# petitAVR-v1.net
KiCad netlist of a schematic drawn in EAGLE
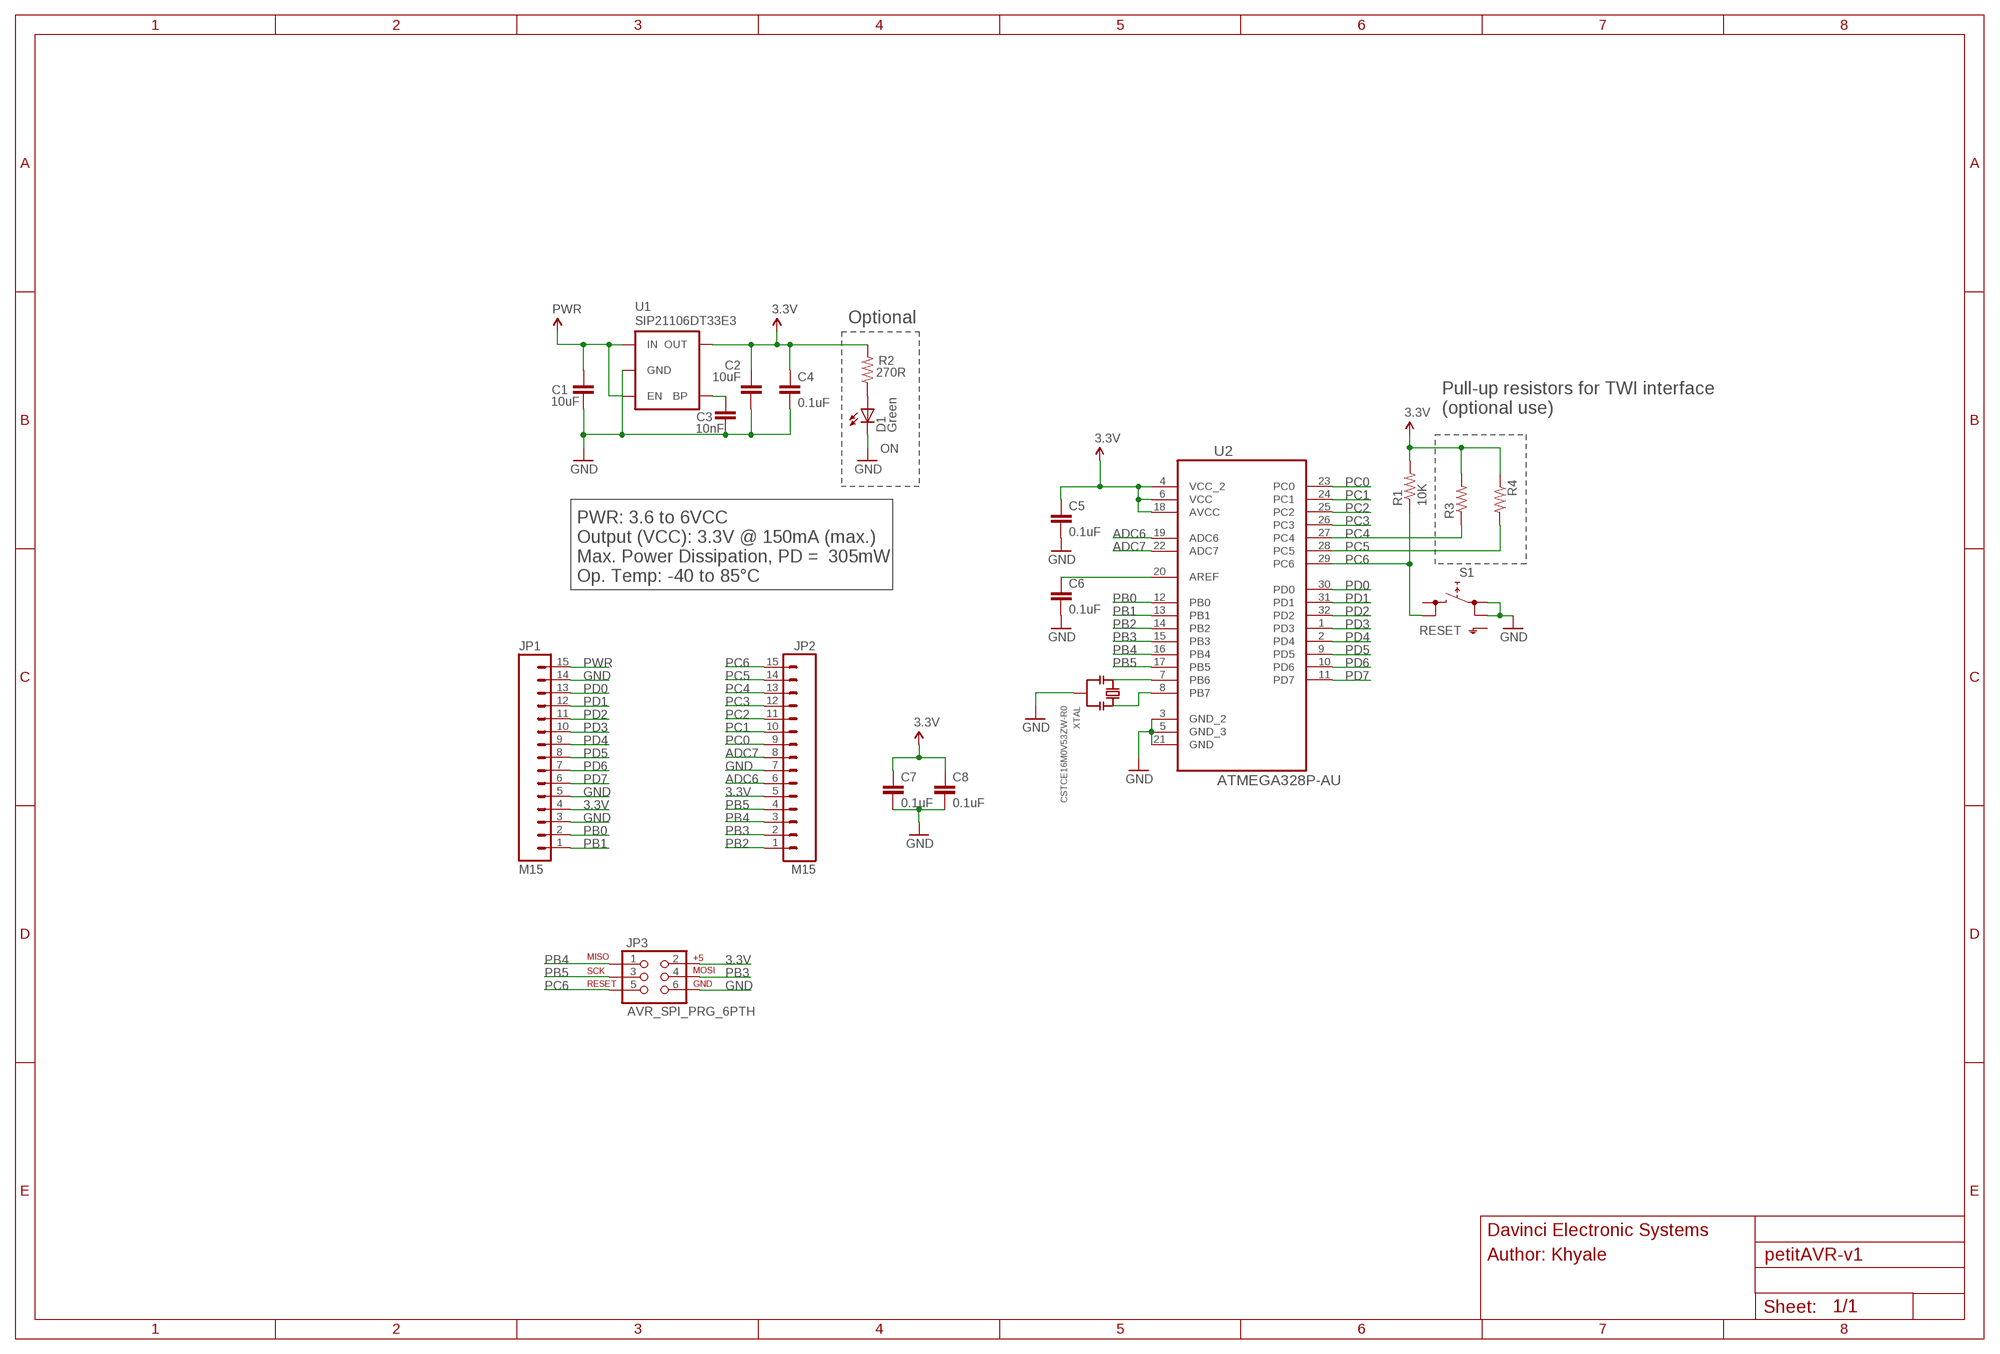
[diagram p0: schematic, sheet 1]

(export (version "E")
  (design (tool "Eeschema 10.0.6"))
  (components
    (comp (ref "C1")
      (value "10uF")
      (footprint "eagle-import:0805")
      (fields (field (name "MPN") "LMK212AB7106MG-T"))
      (libsource (lib "eagle-import") (part "CAP0805"))
    )
    (comp (ref "C2")
      (value "10uF")
      (footprint "eagle-import:0805")
      (fields (field (name "MPN") "LMK212AB7106MG-T"))
      (libsource (lib "eagle-import") (part "CAP0805"))
    )
    (comp (ref "C3")
      (value "10nF")
      (footprint "eagle-import:0805")
      (fields (field (name "MPN") "VJ0805Y103JXQCW1BC"))
      (libsource (lib "eagle-import") (part "CAP0805"))
    )
    (comp (ref "C4")
      (value "0.1uF")
      (footprint "eagle-import:0603-CAP")
      (fields (field (name "MPN") "VJ0603Y104KXJCW1BC"))
      (libsource (lib "eagle-import") (part "SparkFun-Passives_CAP0603-CAP"))
    )
    (comp (ref "C5")
      (value "0.1uF")
      (footprint "eagle-import:0603-CAP")
      (fields (field (name "MPN") "VJ0603Y104KXJCW1BC"))
      (libsource (lib "eagle-import") (part "SparkFun-Passives_CAP0603-CAP"))
    )
    (comp (ref "C6")
      (value "0.1uF")
      (footprint "eagle-import:0603-CAP")
      (fields (field (name "MPN") "VJ0603Y104KXJCW1BC"))
      (libsource (lib "eagle-import") (part "SparkFun-Passives_CAP0603-CAP"))
    )
    (comp (ref "C7")
      (value "0.1uF")
      (footprint "eagle-import:0603-CAP")
      (fields (field (name "MPN") "VJ0603Y104KXJCW1BC"))
      (libsource (lib "eagle-import") (part "SparkFun-Passives_CAP0603-CAP"))
    )
    (comp (ref "C8")
      (value "0.1uF")
      (footprint "eagle-import:0603-CAP")
      (fields (field (name "MPN") "VJ0603Y104KXJCW1BC"))
      (libsource (lib "eagle-import") (part "SparkFun-Passives_CAP0603-CAP"))
    )
    (comp (ref "D1")
      (value "Green")
      (footprint "eagle-import:LED-0603")
      (fields (field (name "MPN") "VLMG1300-GS08"))
      (libsource (lib "eagle-import") (part "LED0603"))
    )
    (comp (ref "JP1")
      (value "M15")
      (footprint "eagle-import:1X15")
      (fields (field (name "MPN") "22-28-4151"))
      (libsource (lib "eagle-import") (part "M15"))
    )
    (comp (ref "JP2")
      (value "M15")
      (footprint "eagle-import:1X15")
      (fields (field (name "MPN") "22-28-4151"))
      (libsource (lib "eagle-import") (part "M15"))
    )
    (comp (ref "JP3")
      (value "AVR_SPI_PRG_6PTH")
      (footprint "eagle-import:2X3")
      (fields (field (name "MPN") "103328-3"))
      (libsource (lib "eagle-import") (part "AVR_SPI_PRG_6PTH"))
    )
    (comp (ref "R1")
      (value "10K")
      (footprint "eagle-import:0603-RES")
      (fields (field (name "MPN") "ERJ-3EKF1002V"))
      (libsource (lib "eagle-import") (part "RESISTOR0603"))
    )
    (comp (ref "R2")
      (value "270R")
      (footprint "eagle-import:0805")
      (fields (field (name "MPN") "ERJ-6GEYJ271V"))
      (libsource (lib "eagle-import") (part "RESISTOR0805-RES"))
    )
    (comp (ref "R3")
      (value "RESISTOR0603-RES")
      (footprint "eagle-import:0603-RES")
      (libsource (lib "eagle-import") (part "RESISTOR0603-RES"))
    )
    (comp (ref "R4")
      (value "RESISTOR0603")
      (footprint "eagle-import:0603-RES")
      (libsource (lib "eagle-import") (part "RESISTOR0603"))
    )
    (comp (ref "S1")
      (value "RESET")
      (footprint "eagle-import:SKHMPXE010")
      (fields (field (name "MPN") "FSM1LPATR"))
      (libsource (lib "eagle-import") (part "SKHMPE010S"))
    )
    (comp (ref "U1")
      (value "SIP21106DT33E3")
      (footprint "eagle-import:SOT23-5")
      (fields (field (name "MPN") "SIP21106DT-33-E3"))
      (libsource (lib "eagle-import") (part "V_REG_LDOSMD"))
    )
    (comp (ref "U2")
      (value "ATMEGA328P-AU")
      (footprint "eagle-import:QFP80P900X900X120-32N")
      (libsource (lib "eagle-import") (part "ATMEGA328P-AU"))
    )
    (comp (ref "XTAL")
      (value "CSTCE16M0V53ZW-R0")
      (footprint "eagle-import:CSTCE_V")
      (libsource (lib "eagle-import") (part "CSTCE16M0V53ZW-R0"))
    )
  )
  (nets
    (net (code "1") (name "/ADC6") (class "Default")
      (node (ref "JP2") (pin "6") (pinfunction "6_6") (pintype "passive"))
      (node (ref "U2") (pin "19") (pinfunction "ADC6_19") (pintype "input"))
    )
    (net (code "2") (name "/ADC7") (class "Default")
      (node (ref "JP2") (pin "8") (pinfunction "8_8") (pintype "passive"))
      (node (ref "U2") (pin "22") (pinfunction "ADC7_22") (pintype "input"))
    )
    (net (code "3") (name "/PB0") (class "Default")
      (node (ref "JP1") (pin "2") (pinfunction "2_2") (pintype "passive"))
      (node (ref "U2") (pin "12") (pinfunction "PB0_12") (pintype "bidirectional"))
    )
    (net (code "4") (name "/PB1") (class "Default")
      (node (ref "JP1") (pin "1") (pinfunction "1_1") (pintype "passive"))
      (node (ref "U2") (pin "13") (pinfunction "PB1_13") (pintype "bidirectional"))
    )
    (net (code "5") (name "/PB2") (class "Default")
      (node (ref "JP2") (pin "1") (pinfunction "1_1") (pintype "passive"))
      (node (ref "U2") (pin "14") (pinfunction "PB2_14") (pintype "bidirectional"))
    )
    (net (code "6") (name "/PB3") (class "Default")
      (node (ref "JP2") (pin "2") (pinfunction "2_2") (pintype "passive"))
      (node (ref "JP3") (pin "4") (pinfunction "4_4") (pintype "passive"))
      (node (ref "U2") (pin "15") (pinfunction "PB3_15") (pintype "bidirectional"))
    )
    (net (code "7") (name "/PB4") (class "Default")
      (node (ref "JP2") (pin "3") (pinfunction "3_3") (pintype "passive"))
      (node (ref "JP3") (pin "1") (pinfunction "1_1") (pintype "passive"))
      (node (ref "U2") (pin "16") (pinfunction "PB4_16") (pintype "bidirectional"))
    )
    (net (code "8") (name "/PB5") (class "Default")
      (node (ref "JP2") (pin "4") (pinfunction "4_4") (pintype "passive"))
      (node (ref "JP3") (pin "3") (pinfunction "3_3") (pintype "passive"))
      (node (ref "U2") (pin "17") (pinfunction "PB5_17") (pintype "bidirectional"))
    )
    (net (code "9") (name "/PC0") (class "Default")
      (node (ref "JP2") (pin "9") (pinfunction "9_9") (pintype "passive"))
      (node (ref "U2") (pin "23") (pinfunction "PC0_23") (pintype "bidirectional"))
    )
    (net (code "10") (name "/PC1") (class "Default")
      (node (ref "JP2") (pin "10") (pinfunction "10_10") (pintype "passive"))
      (node (ref "U2") (pin "24") (pinfunction "PC1_24") (pintype "bidirectional"))
    )
    (net (code "11") (name "/PC2") (class "Default")
      (node (ref "JP2") (pin "11") (pinfunction "11_11") (pintype "passive"))
      (node (ref "U2") (pin "25") (pinfunction "PC2_25") (pintype "bidirectional"))
    )
    (net (code "12") (name "/PC3") (class "Default")
      (node (ref "JP2") (pin "12") (pinfunction "12_12") (pintype "passive"))
      (node (ref "U2") (pin "26") (pinfunction "PC3_26") (pintype "bidirectional"))
    )
    (net (code "13") (name "/PC4") (class "Default")
      (node (ref "JP2") (pin "13") (pinfunction "13_13") (pintype "passive"))
      (node (ref "R3") (pin "1") (pinfunction "1_1") (pintype "passive"))
      (node (ref "U2") (pin "27") (pinfunction "PC4_27") (pintype "bidirectional"))
    )
    (net (code "14") (name "/PC5") (class "Default")
      (node (ref "JP2") (pin "14") (pinfunction "14_14") (pintype "passive"))
      (node (ref "R4") (pin "2") (pinfunction "2_2") (pintype "passive"))
      (node (ref "U2") (pin "28") (pinfunction "PC5_28") (pintype "bidirectional"))
    )
    (net (code "15") (name "/PC6") (class "Default")
      (node (ref "JP2") (pin "15") (pinfunction "15_15") (pintype "passive"))
      (node (ref "JP3") (pin "5") (pinfunction "5_5") (pintype "passive"))
      (node (ref "R1") (pin "1") (pinfunction "1_1") (pintype "passive"))
      (node (ref "S1") (pin "4") (pinfunction "2.2_4") (pintype "passive"))
      (node (ref "U2") (pin "29") (pinfunction "PC6_29") (pintype "bidirectional"))
    )
    (net (code "16") (name "/PD0") (class "Default")
      (node (ref "JP1") (pin "13") (pinfunction "13_13") (pintype "passive"))
      (node (ref "U2") (pin "30") (pinfunction "PD0_30") (pintype "bidirectional"))
    )
    (net (code "17") (name "/PD1") (class "Default")
      (node (ref "JP1") (pin "12") (pinfunction "12_12") (pintype "passive"))
      (node (ref "U2") (pin "31") (pinfunction "PD1_31") (pintype "bidirectional"))
    )
    (net (code "18") (name "/PD2") (class "Default")
      (node (ref "JP1") (pin "11") (pinfunction "11_11") (pintype "passive"))
      (node (ref "U2") (pin "32") (pinfunction "PD2_32") (pintype "bidirectional"))
    )
    (net (code "19") (name "/PD3") (class "Default")
      (node (ref "JP1") (pin "10") (pinfunction "10_10") (pintype "passive"))
      (node (ref "U2") (pin "1") (pinfunction "PD3_1") (pintype "bidirectional"))
    )
    (net (code "20") (name "/PD4") (class "Default")
      (node (ref "JP1") (pin "9") (pinfunction "9_9") (pintype "passive"))
      (node (ref "U2") (pin "2") (pinfunction "PD4_2") (pintype "bidirectional"))
    )
    (net (code "21") (name "/PD5") (class "Default")
      (node (ref "JP1") (pin "8") (pinfunction "8_8") (pintype "passive"))
      (node (ref "U2") (pin "9") (pinfunction "PD5_9") (pintype "bidirectional"))
    )
    (net (code "22") (name "/PD6") (class "Default")
      (node (ref "JP1") (pin "7") (pinfunction "7_7") (pintype "passive"))
      (node (ref "U2") (pin "10") (pinfunction "PD6_10") (pintype "bidirectional"))
    )
    (net (code "23") (name "/PD7") (class "Default")
      (node (ref "JP1") (pin "6") (pinfunction "6_6") (pintype "passive"))
      (node (ref "U2") (pin "11") (pinfunction "PD7_11") (pintype "bidirectional"))
    )
    (net (code "24") (name "3.3V") (class "Default")
      (node (ref "C2") (pin "2") (pinfunction "2_2") (pintype "passive"))
      (node (ref "C4") (pin "1") (pinfunction "1_1") (pintype "passive"))
      (node (ref "C5") (pin "1") (pinfunction "1_1") (pintype "passive"))
      (node (ref "C7") (pin "1") (pinfunction "1_1") (pintype "passive"))
      (node (ref "C8") (pin "1") (pinfunction "1_1") (pintype "passive"))
      (node (ref "JP1") (pin "4") (pinfunction "4_4") (pintype "passive"))
      (node (ref "JP2") (pin "5") (pinfunction "5_5") (pintype "passive"))
      (node (ref "JP3") (pin "2") (pinfunction "2_2") (pintype "passive"))
      (node (ref "R1") (pin "2") (pinfunction "2_2") (pintype "passive"))
      (node (ref "R2") (pin "2") (pinfunction "2_2") (pintype "passive"))
      (node (ref "R3") (pin "2") (pinfunction "2_2") (pintype "passive"))
      (node (ref "R4") (pin "1") (pinfunction "1_1") (pintype "passive"))
      (node (ref "U1") (pin "5") (pinfunction "OUT_5") (pintype "passive"))
      (node (ref "U2") (pin "18") (pinfunction "AVCC_18") (pintype "power_in"))
      (node (ref "U2") (pin "4") (pinfunction "VCC_2_4") (pintype "power_in"))
      (node (ref "U2") (pin "6") (pinfunction "VCC_6") (pintype "power_in"))
    )
    (net (code "25") (name "GND") (class "Default")
      (node (ref "C1") (pin "1") (pinfunction "1_1") (pintype "passive"))
      (node (ref "C2") (pin "1") (pinfunction "1_1") (pintype "passive"))
      (node (ref "C3") (pin "1") (pinfunction "1_1") (pintype "passive"))
      (node (ref "C4") (pin "2") (pinfunction "2_2") (pintype "passive"))
      (node (ref "C5") (pin "2") (pinfunction "2_2") (pintype "passive"))
      (node (ref "C6") (pin "2") (pinfunction "2_2") (pintype "passive"))
      (node (ref "C7") (pin "2") (pinfunction "2_2") (pintype "passive"))
      (node (ref "C8") (pin "2") (pinfunction "2_2") (pintype "passive"))
      (node (ref "D1") (pin "C") (pinfunction "C_C") (pintype "passive"))
      (node (ref "JP1") (pin "14") (pinfunction "14_14") (pintype "passive"))
      (node (ref "JP1") (pin "3") (pinfunction "3_3") (pintype "passive"))
      (node (ref "JP1") (pin "5") (pinfunction "5_5") (pintype "passive"))
      (node (ref "JP2") (pin "7") (pinfunction "7_7") (pintype "passive"))
      (node (ref "JP3") (pin "6") (pinfunction "6_6") (pintype "passive"))
      (node (ref "S1") (pin "1") (pinfunction "1.1_1") (pintype "passive"))
      (node (ref "S1") (pin "2") (pinfunction "1.2_2") (pintype "passive"))
      (node (ref "U1") (pin "2") (pinfunction "GND_2") (pintype "input"))
      (node (ref "U2") (pin "21") (pinfunction "GND_21") (pintype "passive"))
      (node (ref "U2") (pin "3") (pinfunction "GND_2_3") (pintype "passive"))
      (node (ref "U2") (pin "5") (pinfunction "GND_3_5") (pintype "passive"))
      (node (ref "XTAL") (pin "P2") (pinfunction "P2_P2") (pintype "bidirectional"))
    )
    (net (code "26") (name "Net-(D1-PadA)") (class "Default")
      (node (ref "D1") (pin "A") (pinfunction "A_A") (pintype "passive"))
      (node (ref "R2") (pin "1") (pinfunction "1_1") (pintype "passive"))
    )
    (net (code "27") (name "Net-(U1-BP)") (class "Default")
      (node (ref "C3") (pin "2") (pinfunction "2_2") (pintype "passive"))
      (node (ref "U1") (pin "4") (pinfunction "BP_4") (pintype "input"))
    )
    (net (code "28") (name "Net-(U2-AREF)") (class "Default")
      (node (ref "C6") (pin "1") (pinfunction "1_1") (pintype "passive"))
      (node (ref "U2") (pin "20") (pinfunction "AREF_20") (pintype "input"))
    )
    (net (code "29") (name "Net-(U2-PB6)") (class "Default")
      (node (ref "U2") (pin "7") (pinfunction "PB6_7") (pintype "bidirectional"))
      (node (ref "XTAL") (pin "P3") (pinfunction "P3_P3") (pintype "bidirectional"))
    )
    (net (code "30") (name "Net-(U2-PB7)") (class "Default")
      (node (ref "U2") (pin "8") (pinfunction "PB7_8") (pintype "bidirectional"))
      (node (ref "XTAL") (pin "P1") (pinfunction "P1_P1") (pintype "bidirectional"))
    )
    (net (code "31") (name "PWR") (class "Default")
      (node (ref "C1") (pin "2") (pinfunction "2_2") (pintype "passive"))
      (node (ref "JP1") (pin "15") (pinfunction "15_15") (pintype "passive"))
      (node (ref "U1") (pin "1") (pinfunction "IN_1") (pintype "input"))
      (node (ref "U1") (pin "3") (pinfunction "EN_3") (pintype "input"))
    )
    (net (code "32") (name "unconnected-(S1-2.1-Pad3)") (class "Default")
      (node (ref "S1") (pin "3") (pinfunction "2.1_3") (pintype "passive"))
    )
    (net (code "33") (name "unconnected-(S1-SH-Pad5)") (class "Default")
      (node (ref "S1") (pin "5") (pinfunction "SH_5") (pintype "passive"))
    )
  )
)
